# Analog_Channel.net
KiCad netlist of a schematic drawn in Altium Designer
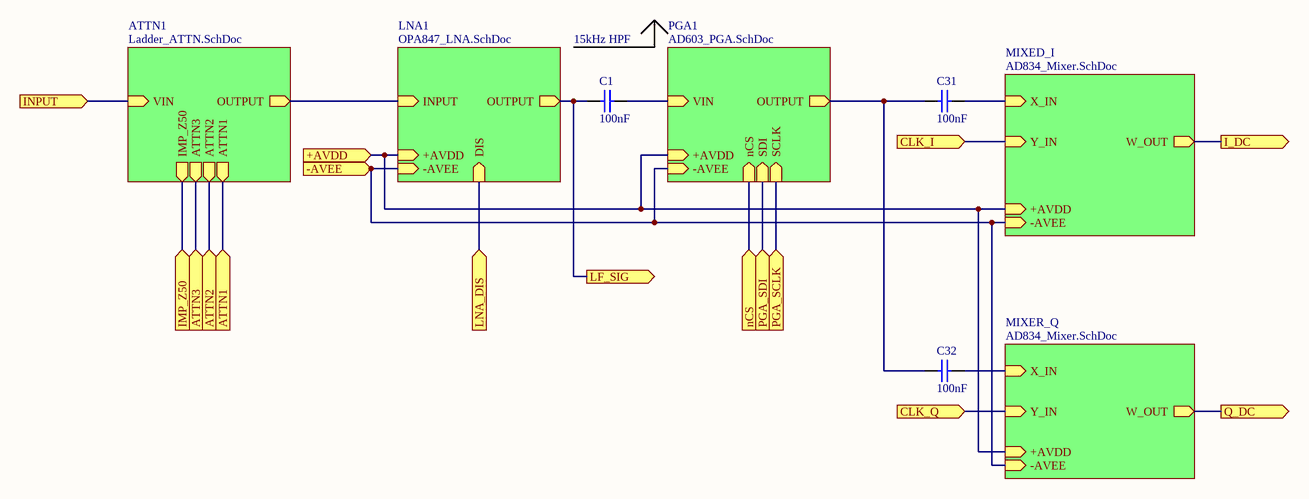
[diagram p0: Analog_Channel.SchDoc]

(export (version "E")
  (design (tool "Eeschema 10.0.6"))
  (components
    (comp (ref "C1")
      (value "100nF")
      (footprint "0805_C")
      (description "贴片电容")
      (libsource (lib "Miscellaneous Devices LC") (part "0805 100nF(104) 10% 50V"))
    )
    (comp (ref "C31")
      (value "100nF")
      (footprint "0805_C")
      (description "贴片电容")
      (libsource (lib "Miscellaneous Devices LC") (part "0805 100nF(104) 10% 50V"))
    )
    (comp (ref "C32")
      (value "100nF")
      (footprint "0805_C")
      (description "贴片电容")
      (libsource (lib "Miscellaneous Devices LC") (part "0805 100nF(104) 10% 50V"))
    )
  )
  (nets
    (net (code "11") (name "/LF_SIG") (class "Default")
      (node (ref "C1") (pin "1") (pinfunction "1_1") (pintype "passive"))
    )
    (net (code "13") (name "/OUTPUT") (class "Default")
      (node (ref "C31") (pin "1") (pinfunction "1_1") (pintype "passive"))
      (node (ref "C32") (pin "1") (pinfunction "1_1") (pintype "passive"))
    )
    (net (code "18") (name "/VIN") (class "Default")
      (node (ref "C1") (pin "2") (pinfunction "2_2") (pintype "passive"))
    )
    (net (code "19") (name "/X_IN") (class "Default")
      (node (ref "C32") (pin "2") (pinfunction "2_2") (pintype "passive"))
    )
    (net (code "20") (name "/X_IN_1") (class "Default")
      (node (ref "C31") (pin "2") (pinfunction "2_2") (pintype "passive"))
    )
  )
)
